# QCopterCAM_PWM_Sch.net
KiCad netlist of a schematic drawn in Altium Designer
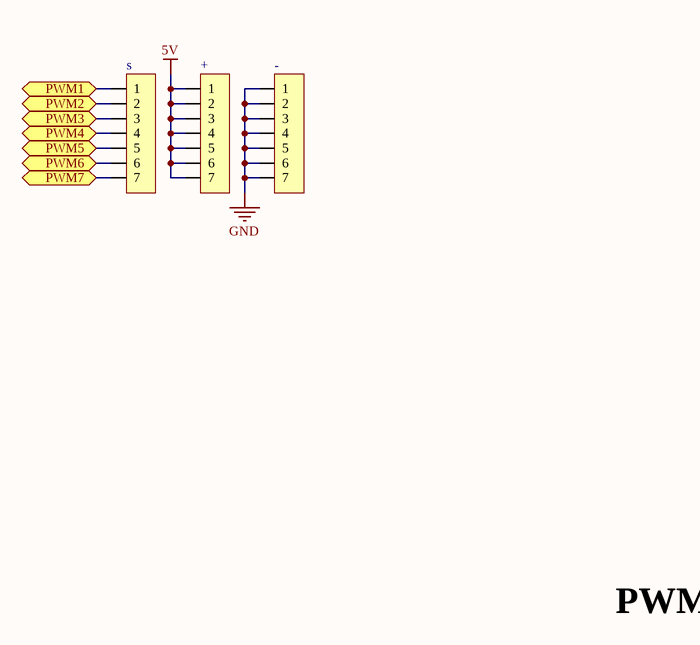
[diagram p0: QCopterCAM_PWM_Sch.SchDoc]

(export (version "E")
  (design (tool "Eeschema 10.0.6"))
  (components
    (comp (ref "+")
      (value "HDR1X7_180_2.54")
      (footprint "PCB_Connector:HDR1X7_180_2.54")
      (description "Header")
      (libsource (lib "SCH_Connector") (part "HDR1X7_180_2.54"))
    )
    (comp (ref "-")
      (value "HDR1X7_180_2.54")
      (footprint "PCB_Connector:HDR1X7_180_2.54")
      (description "Header")
      (libsource (lib "SCH_Connector") (part "HDR1X7_180_2.54"))
    )
    (comp (ref "s")
      (value "HDR1X7_180_2.54")
      (footprint "PCB_Connector:HDR1X7_180_2.54")
      (description "Header")
      (libsource (lib "SCH_Connector") (part "HDR1X7_180_2.54"))
    )
  )
  (nets
    (net (code "1") (name "/PWM1") (class "Default")
      (node (ref "s") (pin "1") (pinfunction "1_1") (pintype "passive"))
    )
    (net (code "2") (name "/PWM2") (class "Default")
      (node (ref "s") (pin "2") (pinfunction "2_2") (pintype "passive"))
    )
    (net (code "3") (name "/PWM3") (class "Default")
      (node (ref "s") (pin "3") (pinfunction "3_3") (pintype "passive"))
    )
    (net (code "4") (name "/PWM4") (class "Default")
      (node (ref "s") (pin "4") (pinfunction "4_4") (pintype "passive"))
    )
    (net (code "5") (name "/PWM5") (class "Default")
      (node (ref "s") (pin "5") (pinfunction "5_5") (pintype "passive"))
    )
    (net (code "6") (name "/PWM6") (class "Default")
      (node (ref "s") (pin "6") (pinfunction "6_6") (pintype "passive"))
    )
    (net (code "7") (name "/PWM7") (class "Default")
      (node (ref "s") (pin "7") (pinfunction "7_7") (pintype "passive"))
    )
    (net (code "8") (name "5V") (class "Default")
      (node (ref "+") (pin "1") (pinfunction "1_1") (pintype "passive"))
      (node (ref "+") (pin "2") (pinfunction "2_2") (pintype "passive"))
      (node (ref "+") (pin "3") (pinfunction "3_3") (pintype "passive"))
      (node (ref "+") (pin "4") (pinfunction "4_4") (pintype "passive"))
      (node (ref "+") (pin "5") (pinfunction "5_5") (pintype "passive"))
      (node (ref "+") (pin "6") (pinfunction "6_6") (pintype "passive"))
      (node (ref "+") (pin "7") (pinfunction "7_7") (pintype "passive"))
    )
    (net (code "9") (name "GND") (class "Default")
      (node (ref "-") (pin "1") (pinfunction "1_1") (pintype "passive"))
      (node (ref "-") (pin "2") (pinfunction "2_2") (pintype "passive"))
      (node (ref "-") (pin "3") (pinfunction "3_3") (pintype "passive"))
      (node (ref "-") (pin "4") (pinfunction "4_4") (pintype "passive"))
      (node (ref "-") (pin "5") (pinfunction "5_5") (pintype "passive"))
      (node (ref "-") (pin "6") (pinfunction "6_6") (pintype "passive"))
      (node (ref "-") (pin "7") (pinfunction "7_7") (pintype "passive"))
    )
  )
)
